# AUX1.net
KiCad netlist of a schematic drawn in Altium Designer
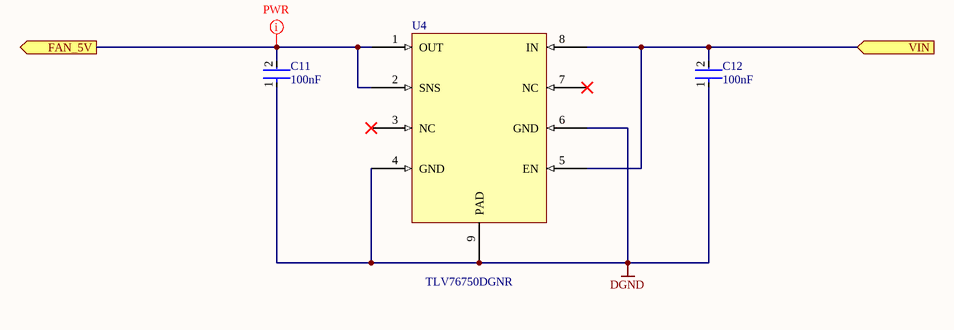
[diagram p0: AUX1.SchDoc]

(export (version "E")
  (design (tool "Eeschema 10.0.6"))
  (components
    (comp (ref "C11")
      (value "100nF")
      (footprint "FP-CC0402-IPC_B")
      (fields (field (name "Comment") "CC0402KRX7R9BB104"))
      (libsource (lib "Digital Shovel") (part "11868f565c42a9108669ba33697ecf6"))
    )
    (comp (ref "C12")
      (value "100nF")
      (footprint "FP-CC0402-IPC_B")
      (fields (field (name "Comment") "CC0402KRX7R9BB104"))
      (libsource (lib "Digital Shovel") (part "11868f565c42a9108669ba33697ecf6"))
    )
    (comp (ref "U4")
      (value "TLV76750DGNR")
      (footprint "TLV76708DGNR-Footprint-1")
      (fields (field (name "MANUFACTURER") "TI"))
      (libsource (lib "Digital Shovel") (part "TLV76708DGNR-Symbol-1"))
    )
  )
  (nets
    (net (code "1") (name "/FAN_5V") (class "Default")
      (node (ref "C11") (pin "2") (pinfunction "2_2") (pintype "passive"))
      (node (ref "U4") (pin "1") (pinfunction "OUT_1") (pintype "input"))
      (node (ref "U4") (pin "2") (pinfunction "SNS_2") (pintype "input"))
    )
    (net (code "2") (name "/VIN") (class "Default")
      (node (ref "C12") (pin "2") (pinfunction "2_2") (pintype "passive"))
      (node (ref "U4") (pin "5") (pinfunction "EN_5") (pintype "input"))
      (node (ref "U4") (pin "8") (pinfunction "IN_8") (pintype "input"))
    )
    (net (code "3") (name "DGND") (class "Default")
      (node (ref "C11") (pin "1") (pinfunction "1_1") (pintype "passive"))
      (node (ref "C12") (pin "1") (pinfunction "1_1") (pintype "passive"))
      (node (ref "U4") (pin "4") (pinfunction "GND_4") (pintype "input"))
      (node (ref "U4") (pin "6") (pinfunction "GND_6") (pintype "input"))
      (node (ref "U4") (pin "9") (pinfunction "PAD_9") (pintype "passive"))
    )
    (net (code "4") (name "unconnected-(U4-NC-Pad3)") (class "Default")
      (node (ref "U4") (pin "3") (pinfunction "NC_3") (pintype "input+no_connect"))
    )
    (net (code "5") (name "unconnected-(U4-NC-Pad7)") (class "Default")
      (node (ref "U4") (pin "7") (pinfunction "NC_7") (pintype "input+no_connect"))
    )
  )
)
